# brick_analog_button.net
KiCad netlist of a schematic drawn in EAGLE
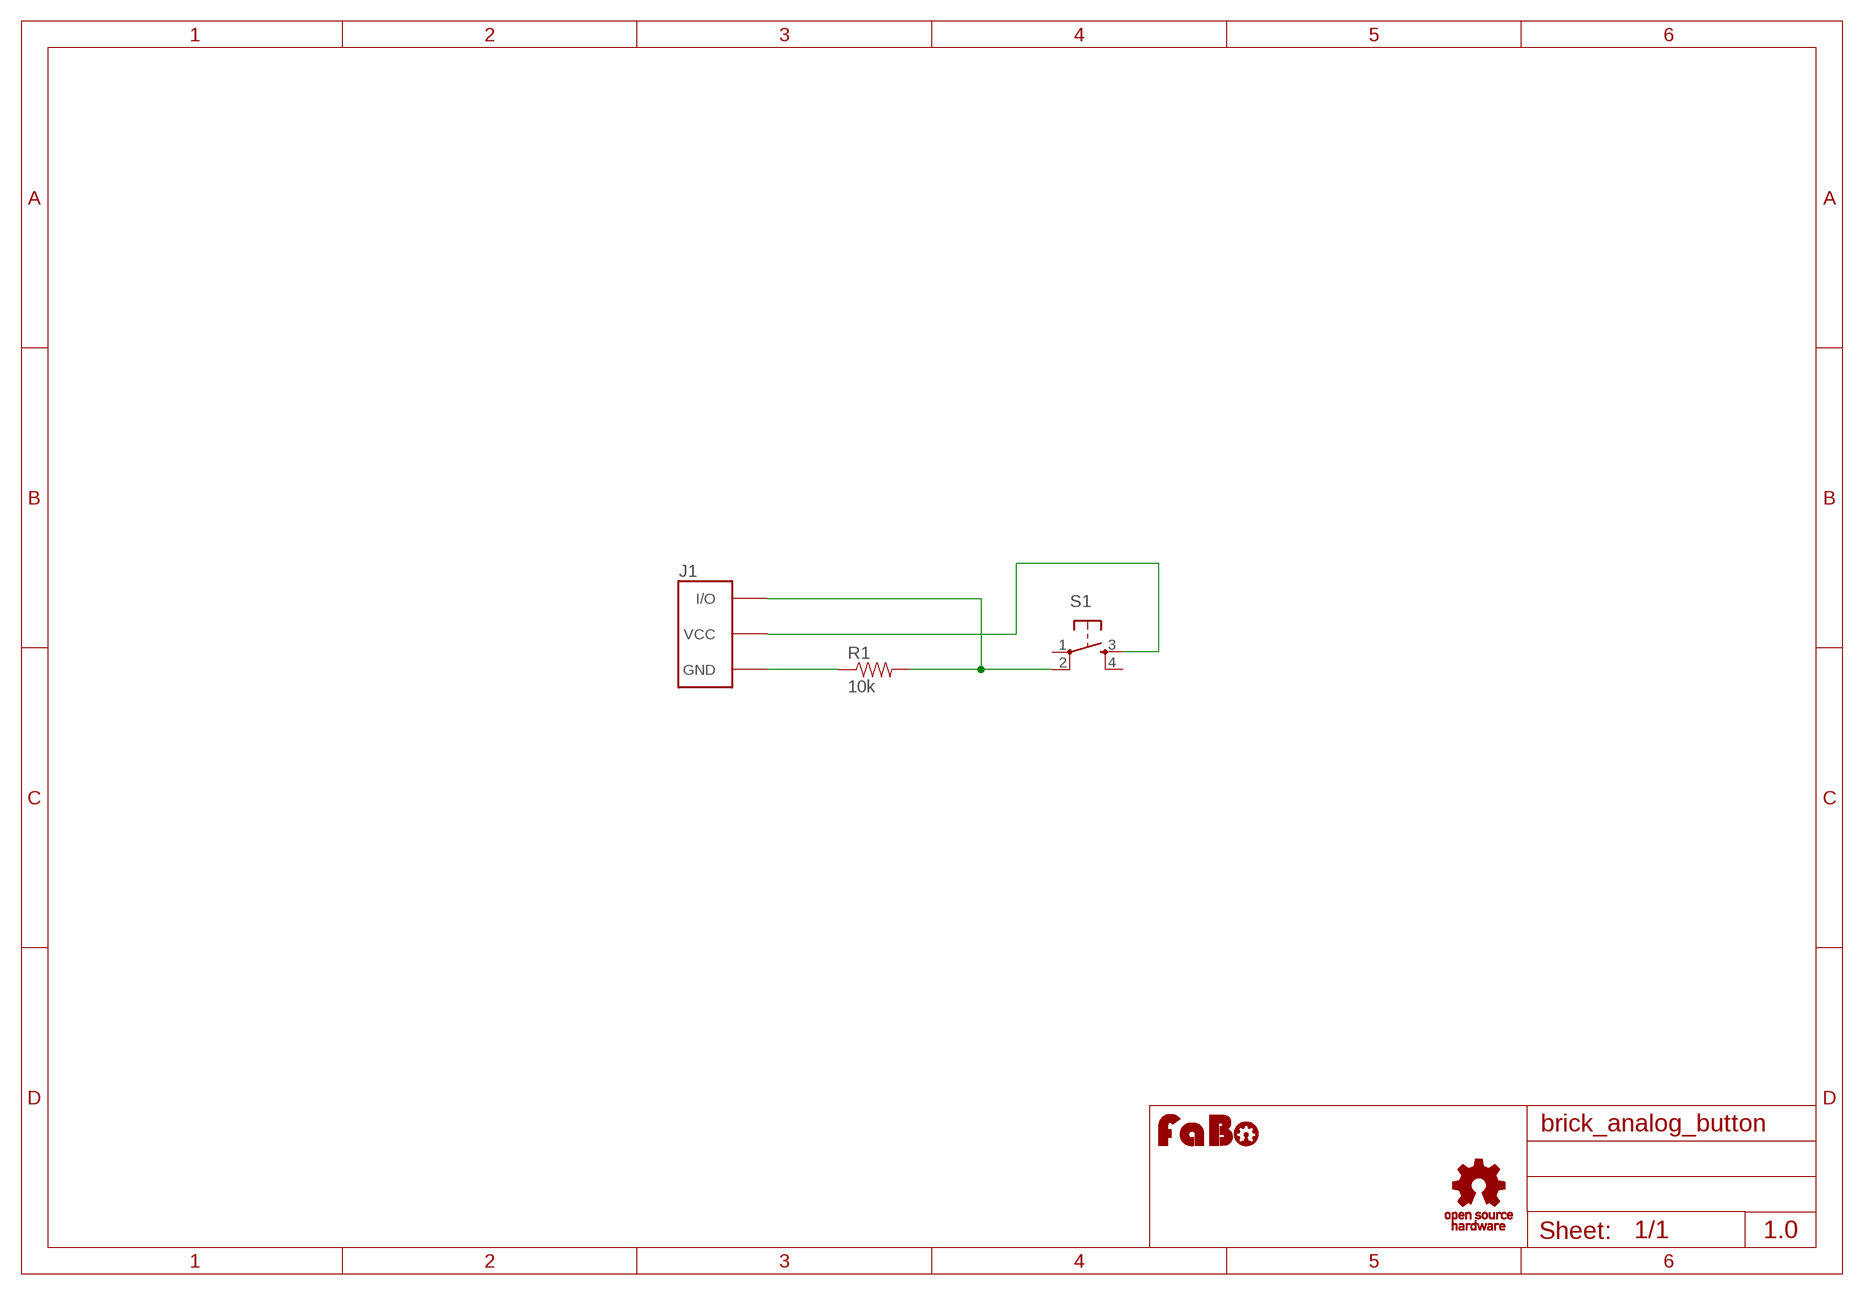
[diagram p0: schematic, sheet 1]

(export (version "E")
  (design (tool "Eeschema 10.0.6"))
  (components
    (comp (ref "J1")
      (value "BRICK_3PIN_NORMAL")
      (footprint "eagle-import:BRICK_3PIN")
      (libsource (lib "eagle-import") (part "BRICK_3PIN_NORMAL"))
    )
    (comp (ref "R1")
      (value "10k")
      (footprint "eagle-import:RES-AXL-REGULAR")
      (libsource (lib "eagle-import") (part "RES-PTH-REGULAR"))
    )
    (comp (ref "S1")
      (value "SWITCH-TACT-6MM")
      (footprint "eagle-import:DTS_6_V")
      (libsource (lib "eagle-import") (part "SWITCH-TACT-6MM"))
    )
    (comp (ref "U$2")
      (value "LOGO_FABO-M")
      (footprint "eagle-import:LOGO_FABO_M")
      (libsource (lib "eagle-import") (part "LOGO_FABO-M"))
    )
    (comp (ref "U$3")
      (value "LOGO_OSHW_T-M")
      (footprint "eagle-import:LOGO_OSHW_T_M")
      (libsource (lib "eagle-import") (part "LOGO_OSHW_T-M"))
    )
  )
  (nets
    (net (code "1") (name "Net-(J1-I{slash}O)") (class "Default")
      (node (ref "J1") (pin "IN/OUT") (pinfunction "I/O_IN/OUT") (pintype "bidirectional"))
      (node (ref "R1") (pin "P$2") (pinfunction "2_P$2") (pintype "passive"))
      (node (ref "S1") (pin "2") (pinfunction "2_2") (pintype "passive"))
    )
    (net (code "2") (name "Net-(J1-PadVCC)") (class "Default")
      (node (ref "J1") (pin "VCC") (pinfunction "VCC_VCC") (pintype "bidirectional"))
      (node (ref "S1") (pin "3") (pinfunction "3_3") (pintype "passive"))
    )
    (net (code "3") (name "Net-(R1-1)") (class "Default")
      (node (ref "J1") (pin "GND") (pinfunction "GND_GND") (pintype "bidirectional"))
      (node (ref "R1") (pin "P$1") (pinfunction "1_P$1") (pintype "passive"))
    )
    (net (code "4") (name "unconnected-(S1-Pad1)") (class "Default")
      (node (ref "S1") (pin "1") (pinfunction "1_1") (pintype "passive"))
    )
    (net (code "5") (name "unconnected-(S1-Pad4)") (class "Default")
      (node (ref "S1") (pin "4") (pinfunction "4_4") (pintype "passive"))
    )
  )
)
